# EFS_V1.net
KiCad netlist of a schematic drawn in EAGLE
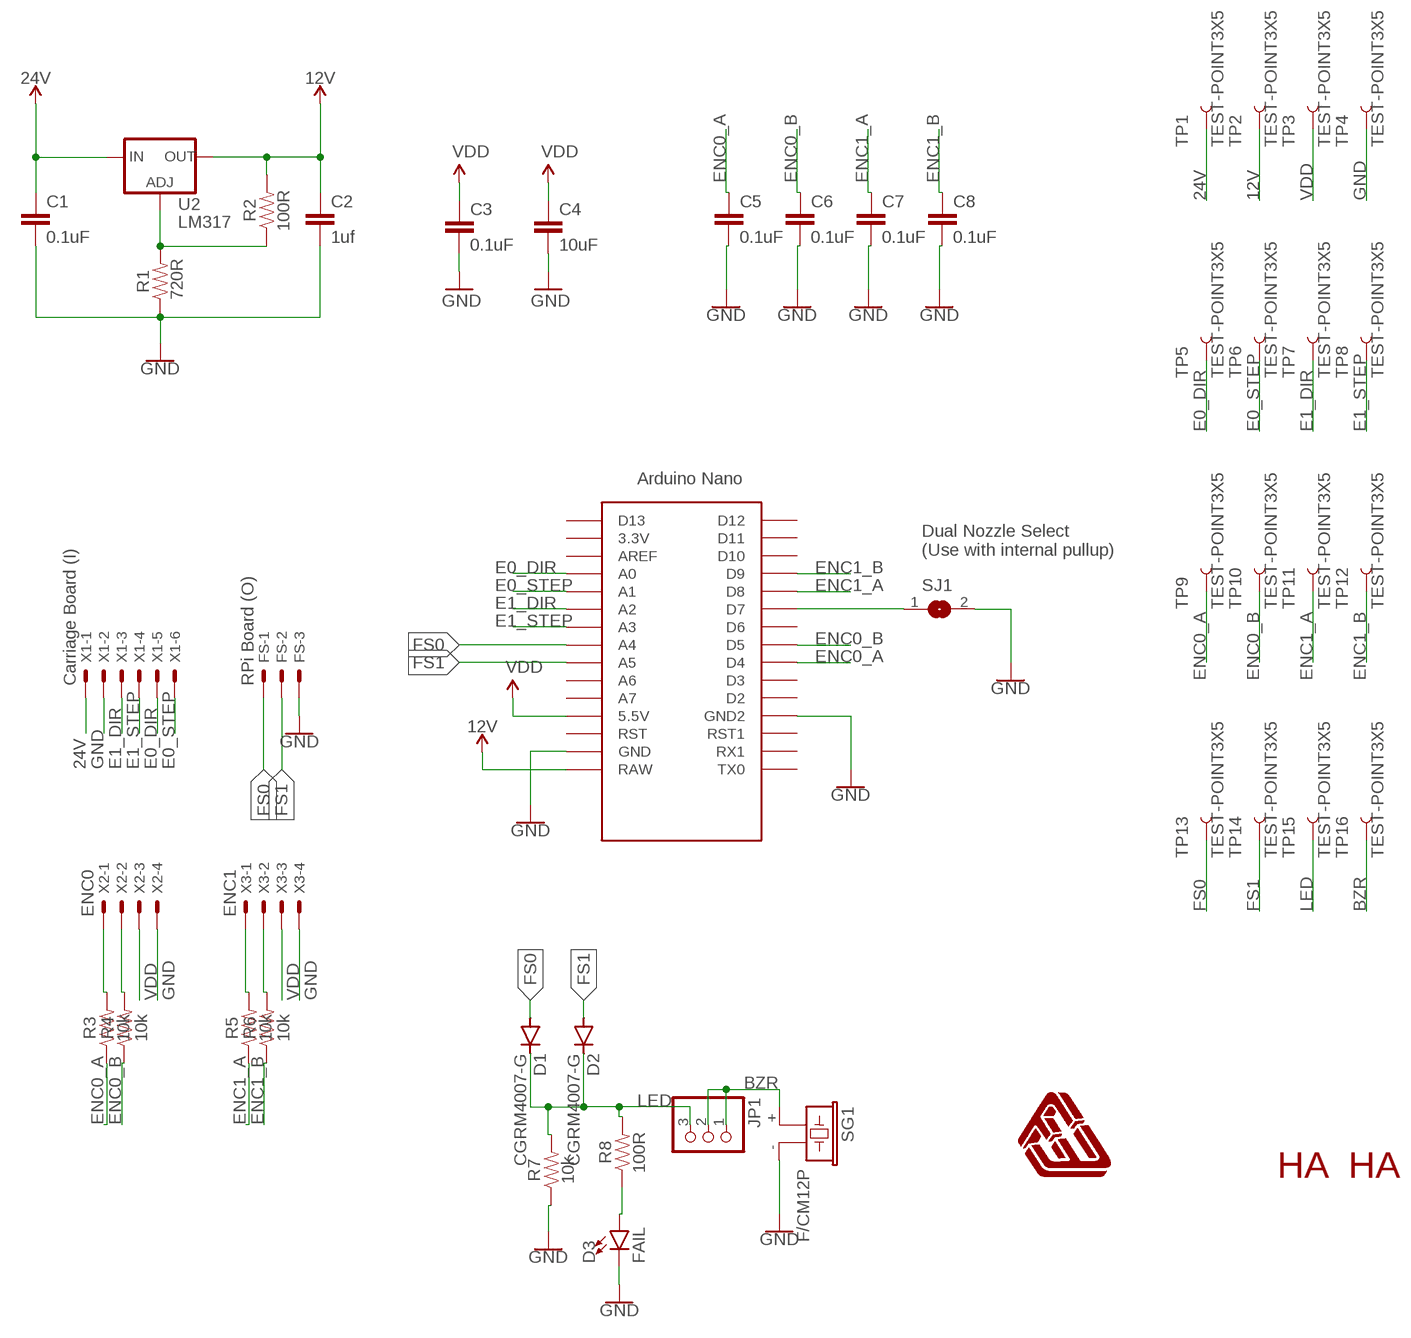
[diagram p0: schematic, sheet 1]

(export (version "E")
  (design (tool "Eeschema 10.0.6"))
  (components
    (comp (ref "C1")
      (value "0.1uF")
      (footprint "eagle-import:0603")
      (libsource (lib "eagle-import") (part "9.0PF-0603-50V-10%"))
    )
    (comp (ref "C2")
      (value "1uf")
      (footprint "eagle-import:0603")
      (libsource (lib "eagle-import") (part "9.0PF-0603-50V-10%"))
    )
    (comp (ref "C3")
      (value "0.1uF")
      (footprint "eagle-import:0603-CAP")
      (libsource (lib "eagle-import") (part "0.1UF-25V-5%(0603)"))
    )
    (comp (ref "C4")
      (value "10uF")
      (footprint "eagle-import:1210")
      (libsource (lib "eagle-import") (part "10UF50V20%(1210)"))
    )
    (comp (ref "C5")
      (value "0.1uF")
      (footprint "eagle-import:0603")
      (libsource (lib "eagle-import") (part "9.0PF-0603-50V-10%"))
    )
    (comp (ref "C6")
      (value "0.1uF")
      (footprint "eagle-import:0603")
      (libsource (lib "eagle-import") (part "9.0PF-0603-50V-10%"))
    )
    (comp (ref "C7")
      (value "0.1uF")
      (footprint "eagle-import:0603")
      (libsource (lib "eagle-import") (part "9.0PF-0603-50V-10%"))
    )
    (comp (ref "C8")
      (value "0.1uF")
      (footprint "eagle-import:0603")
      (libsource (lib "eagle-import") (part "9.0PF-0603-50V-10%"))
    )
    (comp (ref "D1")
      (value "CGRM4007-G")
      (footprint "eagle-import:SOD-123_MINI-SMA")
      (libsource (lib "eagle-import") (part "CGRM400-G7"))
    )
    (comp (ref "D2")
      (value "CGRM4007-G")
      (footprint "eagle-import:SOD-123_MINI-SMA")
      (libsource (lib "eagle-import") (part "CGRM400-G7"))
    )
    (comp (ref "D3")
      (value "FAIL")
      (footprint "eagle-import:LED_3MM")
      (libsource (lib "eagle-import") (part "LED3MM"))
    )
    (comp (ref "FS")
      (value "RPi Board (O)")
      (footprint "eagle-import:JST-XH-03-PACKAGE-LONG-PAD")
      (libsource (lib "eagle-import") (part "JST-XH-03-PIN-LONG-PAD"))
    )
    (comp (ref "JP1")
      (value "PINHD-1X3")
      (footprint "eagle-import:1X03")
      (libsource (lib "eagle-import") (part "PINHD-1X3"))
    )
    (comp (ref "M_HA_1")
      (value "HA_MARK")
      (footprint "eagle-import:HA_MARK")
      (libsource (lib "eagle-import") (part "HA_MARK"))
    )
    (comp (ref "M_HA_2")
      (value "HA_MARK")
      (footprint "eagle-import:HA_MARK")
      (libsource (lib "eagle-import") (part "HA_MARK"))
    )
    (comp (ref "R1")
      (value "720R")
      (footprint "eagle-import:0603")
      (libsource (lib "eagle-import") (part "RESISTOR0603"))
    )
    (comp (ref "R2")
      (value "100R")
      (footprint "eagle-import:0603")
      (libsource (lib "eagle-import") (part "RESISTOR0603"))
    )
    (comp (ref "R3")
      (value "10k")
      (footprint "eagle-import:0603")
      (libsource (lib "eagle-import") (part "RESISTOR0603"))
    )
    (comp (ref "R4")
      (value "10k")
      (footprint "eagle-import:0603")
      (libsource (lib "eagle-import") (part "RESISTOR0603"))
    )
    (comp (ref "R5")
      (value "10k")
      (footprint "eagle-import:0603")
      (libsource (lib "eagle-import") (part "RESISTOR0603"))
    )
    (comp (ref "R6")
      (value "10k")
      (footprint "eagle-import:0603")
      (libsource (lib "eagle-import") (part "RESISTOR0603"))
    )
    (comp (ref "R7")
      (value "10k")
      (footprint "eagle-import:0603")
      (libsource (lib "eagle-import") (part "RESISTOR0603"))
    )
    (comp (ref "R8")
      (value "100R")
      (footprint "eagle-import:0603")
      (libsource (lib "eagle-import") (part "RESISTOR0603"))
    )
    (comp (ref "SG1")
      (value "F/CM12P")
      (footprint "eagle-import:F_CM12P")
      (libsource (lib "eagle-import") (part "F/CM12P"))
    )
    (comp (ref "SJ1")
      (value "SJW")
      (footprint "eagle-import:SJW")
      (libsource (lib "eagle-import") (part "SJW"))
    )
    (comp (ref "TP1")
      (value "TEST-POINT3X5")
      (footprint "eagle-import:PAD.03X.05")
      (libsource (lib "eagle-import") (part "TEST-POINT3X5"))
    )
    (comp (ref "TP2")
      (value "TEST-POINT3X5")
      (footprint "eagle-import:PAD.03X.05")
      (libsource (lib "eagle-import") (part "TEST-POINT3X5"))
    )
    (comp (ref "TP3")
      (value "TEST-POINT3X5")
      (footprint "eagle-import:PAD.03X.05")
      (libsource (lib "eagle-import") (part "TEST-POINT3X5"))
    )
    (comp (ref "TP4")
      (value "TEST-POINT3X5")
      (footprint "eagle-import:PAD.03X.05")
      (libsource (lib "eagle-import") (part "TEST-POINT3X5"))
    )
    (comp (ref "TP5")
      (value "TEST-POINT3X5")
      (footprint "eagle-import:PAD.03X.05")
      (libsource (lib "eagle-import") (part "TEST-POINT3X5"))
    )
    (comp (ref "TP6")
      (value "TEST-POINT3X5")
      (footprint "eagle-import:PAD.03X.05")
      (libsource (lib "eagle-import") (part "TEST-POINT3X5"))
    )
    (comp (ref "TP7")
      (value "TEST-POINT3X5")
      (footprint "eagle-import:PAD.03X.05")
      (libsource (lib "eagle-import") (part "TEST-POINT3X5"))
    )
    (comp (ref "TP8")
      (value "TEST-POINT3X5")
      (footprint "eagle-import:PAD.03X.05")
      (libsource (lib "eagle-import") (part "TEST-POINT3X5"))
    )
    (comp (ref "TP9")
      (value "TEST-POINT3X5")
      (footprint "eagle-import:PAD.03X.05")
      (libsource (lib "eagle-import") (part "TEST-POINT3X5"))
    )
    (comp (ref "TP10")
      (value "TEST-POINT3X5")
      (footprint "eagle-import:PAD.03X.05")
      (libsource (lib "eagle-import") (part "TEST-POINT3X5"))
    )
    (comp (ref "TP11")
      (value "TEST-POINT3X5")
      (footprint "eagle-import:PAD.03X.05")
      (libsource (lib "eagle-import") (part "TEST-POINT3X5"))
    )
    (comp (ref "TP12")
      (value "TEST-POINT3X5")
      (footprint "eagle-import:PAD.03X.05")
      (libsource (lib "eagle-import") (part "TEST-POINT3X5"))
    )
    (comp (ref "TP13")
      (value "TEST-POINT3X5")
      (footprint "eagle-import:PAD.03X.05")
      (libsource (lib "eagle-import") (part "TEST-POINT3X5"))
    )
    (comp (ref "TP14")
      (value "TEST-POINT3X5")
      (footprint "eagle-import:PAD.03X.05")
      (libsource (lib "eagle-import") (part "TEST-POINT3X5"))
    )
    (comp (ref "TP15")
      (value "TEST-POINT3X5")
      (footprint "eagle-import:PAD.03X.05")
      (libsource (lib "eagle-import") (part "TEST-POINT3X5"))
    )
    (comp (ref "TP16")
      (value "TEST-POINT3X5")
      (footprint "eagle-import:PAD.03X.05")
      (libsource (lib "eagle-import") (part "TEST-POINT3X5"))
    )
    (comp (ref "U$1")
      (value "NANO")
      (footprint "eagle-import:NANO")
      (libsource (lib "eagle-import") (part "NANO"))
    )
    (comp (ref "U$2")
      (value "FWLOGO")
      (footprint "eagle-import:FWLOGO")
      (libsource (lib "eagle-import") (part "FWLOGO"))
    )
    (comp (ref "U2")
      (value "LM317")
      (footprint "eagle-import:SOT223")
      (libsource (lib "eagle-import") (part "V_REG_317SMD"))
    )
    (comp (ref "X1")
      (value "Carriage Board (I)")
      (footprint "eagle-import:JST-XH-06-PACKAGE-LONG-PAD")
      (libsource (lib "eagle-import") (part "JST-XH-06-PIN-LONG-PAD"))
    )
    (comp (ref "X2")
      (value "ENC0")
      (footprint "eagle-import:JST-XH-04-PACKAGE-LONG-PAD")
      (libsource (lib "eagle-import") (part "JST-XH-04-PIN-LONG-PAD"))
    )
    (comp (ref "X3")
      (value "ENC1")
      (footprint "eagle-import:JST-XH-04-PACKAGE-LONG-PAD")
      (libsource (lib "eagle-import") (part "JST-XH-04-PIN-LONG-PAD"))
    )
  )
  (nets
    (net (code "1") (name "/BZR") (class "Default")
      (node (ref "JP1") (pin "1") (pinfunction "1_1") (pintype "passive"))
      (node (ref "JP1") (pin "2") (pinfunction "2_2") (pintype "passive"))
      (node (ref "SG1") (pin "+") (pinfunction "1_+") (pintype "passive"))
      (node (ref "TP16") (pin "P$1") (pinfunction "1_P$1") (pintype "bidirectional"))
    )
    (net (code "2") (name "/E0_DIR") (class "Default")
      (node (ref "TP5") (pin "P$1") (pinfunction "1_P$1") (pintype "bidirectional"))
      (node (ref "U$1") (pin "A0") (pinfunction "A0_A0") (pintype "bidirectional"))
      (node (ref "X1") (pin "5") (pinfunction "S_5") (pintype "passive"))
    )
    (net (code "3") (name "/E0_STEP") (class "Default")
      (node (ref "TP6") (pin "P$1") (pinfunction "1_P$1") (pintype "bidirectional"))
      (node (ref "U$1") (pin "A1") (pinfunction "A1_A1") (pintype "bidirectional"))
      (node (ref "X1") (pin "6") (pinfunction "S_6") (pintype "passive"))
    )
    (net (code "4") (name "/E1_DIR") (class "Default")
      (node (ref "TP7") (pin "P$1") (pinfunction "1_P$1") (pintype "bidirectional"))
      (node (ref "U$1") (pin "A2") (pinfunction "A2_A2") (pintype "bidirectional"))
      (node (ref "X1") (pin "3") (pinfunction "S_3") (pintype "passive"))
    )
    (net (code "5") (name "/E1_STEP") (class "Default")
      (node (ref "TP8") (pin "P$1") (pinfunction "1_P$1") (pintype "bidirectional"))
      (node (ref "U$1") (pin "A3") (pinfunction "A3_A3") (pintype "bidirectional"))
      (node (ref "X1") (pin "4") (pinfunction "S_4") (pintype "passive"))
    )
    (net (code "6") (name "/ENC0_A") (class "Default")
      (node (ref "C5") (pin "1") (pinfunction "1_1") (pintype "passive"))
      (node (ref "R3") (pin "1") (pinfunction "1_1") (pintype "passive"))
      (node (ref "TP9") (pin "P$1") (pinfunction "1_P$1") (pintype "bidirectional"))
      (node (ref "U$1") (pin "D4") (pinfunction "D4_D4") (pintype "bidirectional"))
    )
    (net (code "7") (name "/ENC0_B") (class "Default")
      (node (ref "C6") (pin "1") (pinfunction "1_1") (pintype "passive"))
      (node (ref "R4") (pin "1") (pinfunction "1_1") (pintype "passive"))
      (node (ref "TP10") (pin "P$1") (pinfunction "1_P$1") (pintype "bidirectional"))
      (node (ref "U$1") (pin "D5") (pinfunction "D5_D5") (pintype "bidirectional"))
    )
    (net (code "8") (name "/ENC1_A") (class "Default")
      (node (ref "C7") (pin "1") (pinfunction "1_1") (pintype "passive"))
      (node (ref "R5") (pin "1") (pinfunction "1_1") (pintype "passive"))
      (node (ref "TP11") (pin "P$1") (pinfunction "1_P$1") (pintype "bidirectional"))
      (node (ref "U$1") (pin "D8") (pinfunction "D8_D8") (pintype "bidirectional"))
    )
    (net (code "9") (name "/ENC1_B") (class "Default")
      (node (ref "C8") (pin "1") (pinfunction "1_1") (pintype "passive"))
      (node (ref "R6") (pin "1") (pinfunction "1_1") (pintype "passive"))
      (node (ref "TP12") (pin "P$1") (pinfunction "1_P$1") (pintype "bidirectional"))
      (node (ref "U$1") (pin "D9") (pinfunction "D9_D9") (pintype "bidirectional"))
    )
    (net (code "10") (name "/LED") (class "Default")
      (node (ref "D1") (pin "C") (pinfunction "C_C") (pintype "passive"))
      (node (ref "D2") (pin "C") (pinfunction "C_C") (pintype "passive"))
      (node (ref "JP1") (pin "3") (pinfunction "3_3") (pintype "passive"))
      (node (ref "R7") (pin "2") (pinfunction "2_2") (pintype "passive"))
      (node (ref "R8") (pin "2") (pinfunction "2_2") (pintype "passive"))
      (node (ref "TP15") (pin "P$1") (pinfunction "1_P$1") (pintype "bidirectional"))
    )
    (net (code "11") (name "12V") (class "Default")
      (node (ref "C2") (pin "1") (pinfunction "1_1") (pintype "passive"))
      (node (ref "R2") (pin "2") (pinfunction "2_2") (pintype "passive"))
      (node (ref "TP2") (pin "P$1") (pinfunction "1_P$1") (pintype "bidirectional"))
      (node (ref "U$1") (pin "RAW") (pinfunction "RAW_RAW") (pintype "bidirectional"))
      (node (ref "U2") (pin "2") (pinfunction "OUT_2") (pintype "output"))
    )
    (net (code "12") (name "24V") (class "Default")
      (node (ref "C1") (pin "1") (pinfunction "1_1") (pintype "passive"))
      (node (ref "TP1") (pin "P$1") (pinfunction "1_P$1") (pintype "bidirectional"))
      (node (ref "U2") (pin "3") (pinfunction "IN_3") (pintype "input"))
      (node (ref "X1") (pin "1") (pinfunction "S_1") (pintype "passive"))
    )
    (net (code "13") (name "FS0") (class "Default")
      (node (ref "D1") (pin "A") (pinfunction "A_A") (pintype "passive"))
      (node (ref "FS") (pin "1") (pinfunction "S_1") (pintype "passive"))
      (node (ref "TP13") (pin "P$1") (pinfunction "1_P$1") (pintype "bidirectional"))
      (node (ref "U$1") (pin "A4") (pinfunction "A4_A4") (pintype "bidirectional"))
    )
    (net (code "14") (name "FS1") (class "Default")
      (node (ref "D2") (pin "A") (pinfunction "A_A") (pintype "passive"))
      (node (ref "FS") (pin "2") (pinfunction "S_2") (pintype "passive"))
      (node (ref "TP14") (pin "P$1") (pinfunction "1_P$1") (pintype "bidirectional"))
      (node (ref "U$1") (pin "A5") (pinfunction "A5_A5") (pintype "bidirectional"))
    )
    (net (code "15") (name "GND") (class "Default")
      (node (ref "C1") (pin "2") (pinfunction "2_2") (pintype "passive"))
      (node (ref "C2") (pin "2") (pinfunction "2_2") (pintype "passive"))
      (node (ref "C3") (pin "2") (pinfunction "2_2") (pintype "passive"))
      (node (ref "C4") (pin "2") (pinfunction "2_2") (pintype "passive"))
      (node (ref "C5") (pin "2") (pinfunction "2_2") (pintype "passive"))
      (node (ref "C6") (pin "2") (pinfunction "2_2") (pintype "passive"))
      (node (ref "C7") (pin "2") (pinfunction "2_2") (pintype "passive"))
      (node (ref "C8") (pin "2") (pinfunction "2_2") (pintype "passive"))
      (node (ref "D3") (pin "K") (pinfunction "C_K") (pintype "passive"))
      (node (ref "FS") (pin "3") (pinfunction "S_3") (pintype "passive"))
      (node (ref "R1") (pin "1") (pinfunction "1_1") (pintype "passive"))
      (node (ref "R7") (pin "1") (pinfunction "1_1") (pintype "passive"))
      (node (ref "SG1") (pin "-") (pinfunction "2_-") (pintype "passive"))
      (node (ref "SJ1") (pin "2") (pinfunction "2_2") (pintype "passive"))
      (node (ref "TP4") (pin "P$1") (pinfunction "1_P$1") (pintype "bidirectional"))
      (node (ref "U$1") (pin "GND") (pinfunction "GND_GND") (pintype "bidirectional"))
      (node (ref "U$1") (pin "GND1") (pinfunction "GND2_GND1") (pintype "bidirectional"))
      (node (ref "X1") (pin "2") (pinfunction "S_2") (pintype "passive"))
      (node (ref "X2") (pin "4") (pinfunction "S_4") (pintype "passive"))
      (node (ref "X3") (pin "4") (pinfunction "S_4") (pintype "passive"))
    )
    (net (code "16") (name "Net-(D3-PadA)") (class "Default")
      (node (ref "D3") (pin "A") (pinfunction "A_A") (pintype "passive"))
      (node (ref "R8") (pin "1") (pinfunction "1_1") (pintype "passive"))
    )
    (net (code "17") (name "Net-(SJ1-Pad1)") (class "Default")
      (node (ref "SJ1") (pin "1") (pinfunction "1_1") (pintype "passive"))
      (node (ref "U$1") (pin "D7") (pinfunction "D7_D7") (pintype "bidirectional"))
    )
    (net (code "18") (name "Net-(U2-ADJ)") (class "Default")
      (node (ref "R1") (pin "2") (pinfunction "2_2") (pintype "passive"))
      (node (ref "R2") (pin "1") (pinfunction "1_1") (pintype "passive"))
      (node (ref "U2") (pin "1") (pinfunction "ADJ_1") (pintype "input"))
    )
    (net (code "19") (name "Net-(X2A-S)") (class "Default")
      (node (ref "R3") (pin "2") (pinfunction "2_2") (pintype "passive"))
      (node (ref "X2") (pin "1") (pinfunction "S_1") (pintype "passive"))
    )
    (net (code "20") (name "Net-(X2B-S)") (class "Default")
      (node (ref "R4") (pin "2") (pinfunction "2_2") (pintype "passive"))
      (node (ref "X2") (pin "2") (pinfunction "S_2") (pintype "passive"))
    )
    (net (code "21") (name "Net-(X3A-S)") (class "Default")
      (node (ref "R5") (pin "2") (pinfunction "2_2") (pintype "passive"))
      (node (ref "X3") (pin "1") (pinfunction "S_1") (pintype "passive"))
    )
    (net (code "22") (name "Net-(X3B-S)") (class "Default")
      (node (ref "R6") (pin "2") (pinfunction "2_2") (pintype "passive"))
      (node (ref "X3") (pin "2") (pinfunction "S_2") (pintype "passive"))
    )
    (net (code "23") (name "VDD") (class "Default")
      (node (ref "C3") (pin "1") (pinfunction "1_1") (pintype "passive"))
      (node (ref "C4") (pin "1") (pinfunction "1_1") (pintype "passive"))
      (node (ref "TP3") (pin "P$1") (pinfunction "1_P$1") (pintype "bidirectional"))
      (node (ref "U$1") (pin "5V") (pinfunction "5.5V_5V") (pintype "bidirectional"))
      (node (ref "X2") (pin "3") (pinfunction "S_3") (pintype "passive"))
      (node (ref "X3") (pin "3") (pinfunction "S_3") (pintype "passive"))
    )
    (net (code "24") (name "unconnected-(U$1-Pad3.3V)") (class "Default")
      (node (ref "U$1") (pin "3.3V") (pinfunction "3.3V_3.3V") (pintype "bidirectional"))
    )
    (net (code "25") (name "unconnected-(U$1-PadA6)") (class "Default")
      (node (ref "U$1") (pin "A6") (pinfunction "A6_A6") (pintype "bidirectional"))
    )
    (net (code "26") (name "unconnected-(U$1-PadA7)") (class "Default")
      (node (ref "U$1") (pin "A7") (pinfunction "A7_A7") (pintype "bidirectional"))
    )
    (net (code "27") (name "unconnected-(U$1-PadAREF)") (class "Default")
      (node (ref "U$1") (pin "AREF") (pinfunction "AREF_AREF") (pintype "bidirectional"))
    )
    (net (code "28") (name "unconnected-(U$1-PadD2)") (class "Default")
      (node (ref "U$1") (pin "D2") (pinfunction "D2_D2") (pintype "bidirectional"))
    )
    (net (code "29") (name "unconnected-(U$1-PadD3)") (class "Default")
      (node (ref "U$1") (pin "D3") (pinfunction "D3_D3") (pintype "bidirectional"))
    )
    (net (code "30") (name "unconnected-(U$1-PadD6)") (class "Default")
      (node (ref "U$1") (pin "D6") (pinfunction "D6_D6") (pintype "bidirectional"))
    )
    (net (code "31") (name "unconnected-(U$1-PadD10)") (class "Default")
      (node (ref "U$1") (pin "D10") (pinfunction "D10_D10") (pintype "bidirectional"))
    )
    (net (code "32") (name "unconnected-(U$1-PadD11)") (class "Default")
      (node (ref "U$1") (pin "D11") (pinfunction "D11_D11") (pintype "bidirectional"))
    )
    (net (code "33") (name "unconnected-(U$1-PadD12)") (class "Default")
      (node (ref "U$1") (pin "D12") (pinfunction "D12_D12") (pintype "bidirectional"))
    )
    (net (code "34") (name "unconnected-(U$1-PadD13)") (class "Default")
      (node (ref "U$1") (pin "D13") (pinfunction "D13_D13") (pintype "bidirectional"))
    )
    (net (code "35") (name "unconnected-(U$1-PadICSP1)") (class "Default")
      (node (ref "U$1") (pin "ICSP1") (pinfunction "ICSP1_ICSP1") (pintype "bidirectional"))
    )
    (net (code "36") (name "unconnected-(U$1-PadICSP2)") (class "Default")
      (node (ref "U$1") (pin "ICSP2") (pinfunction "ICSP2_ICSP2") (pintype "bidirectional"))
    )
    (net (code "37") (name "unconnected-(U$1-PadICSP3)") (class "Default")
      (node (ref "U$1") (pin "ICSP3") (pinfunction "ICSP3_ICSP3") (pintype "bidirectional"))
    )
    (net (code "38") (name "unconnected-(U$1-PadICSP4)") (class "Default")
      (node (ref "U$1") (pin "ICSP4") (pinfunction "ICSP4_ICSP4") (pintype "bidirectional"))
    )
    (net (code "39") (name "unconnected-(U$1-PadICSP5)") (class "Default")
      (node (ref "U$1") (pin "ICSP5") (pinfunction "ICSP5_ICSP5") (pintype "bidirectional"))
    )
    (net (code "40") (name "unconnected-(U$1-PadICSP6)") (class "Default")
      (node (ref "U$1") (pin "ICSP6") (pinfunction "ICSP6_ICSP6") (pintype "bidirectional"))
    )
    (net (code "41") (name "unconnected-(U$1-PadRST)") (class "Default")
      (node (ref "U$1") (pin "RST") (pinfunction "RST_RST") (pintype "bidirectional"))
    )
    (net (code "42") (name "unconnected-(U$1-PadRST1)") (class "Default")
      (node (ref "U$1") (pin "RST1") (pinfunction "RST1_RST1") (pintype "bidirectional"))
    )
    (net (code "43") (name "unconnected-(U$1-PadRX1)") (class "Default")
      (node (ref "U$1") (pin "RX1") (pinfunction "RX1_RX1") (pintype "bidirectional"))
    )
    (net (code "44") (name "unconnected-(U$1-PadTX0)") (class "Default")
      (node (ref "U$1") (pin "TX0") (pinfunction "TX0_TX0") (pintype "bidirectional"))
    )
  )
)
